# 02_-_GSM.net
KiCad netlist of a schematic drawn in Altium Designer
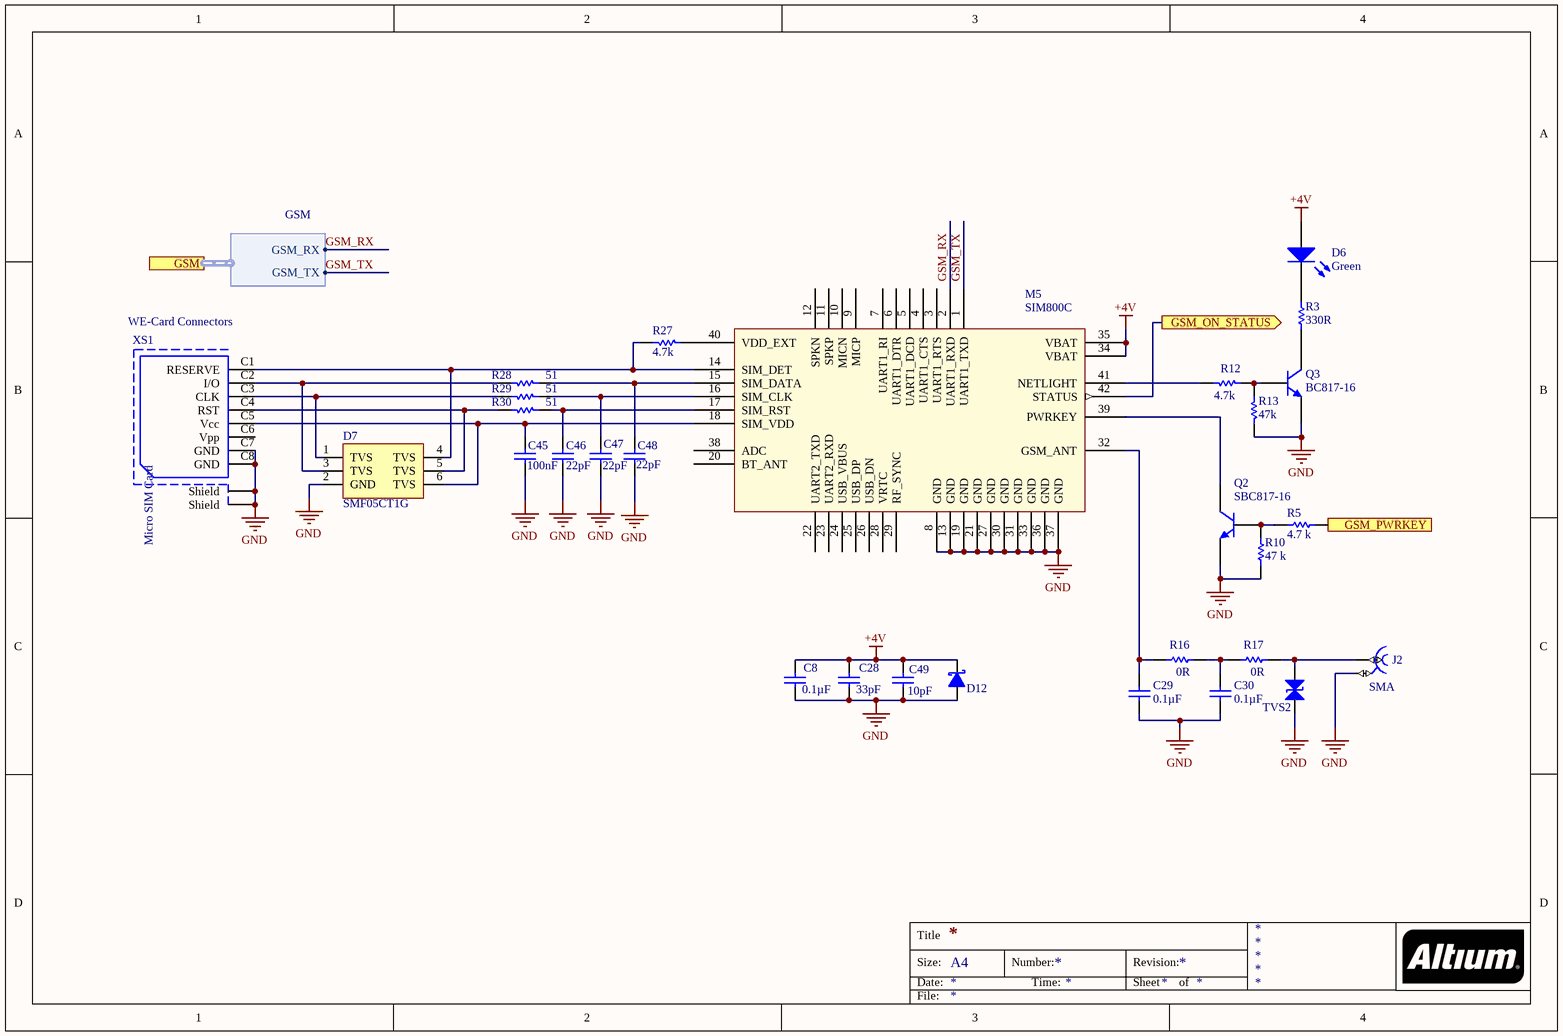
[diagram p0: [02] - GSM.SchDoc]

(export (version "E")
  (design (tool "Eeschema 10.0.6"))
  (components
    (comp (ref "C8")
      (value "Capacitor")
      (footprint "Blue Tractor-2021:0603_C")
      (description "Chip Capacitor Nonpolar")
      (fields
        (field (name "MANUFACTURER") "Kemet")
        (field (name "MANUFACTURER PART NUMBER") "C0603C104K5RACTU")
        (field (name "CAPACITANCE") "0.1µF")
      )
      (libsource (lib "Altium_Library") (part "Capacitor"))
    )
    (comp (ref "C28")
      (value "Capacitor")
      (footprint "Blue Tractor-2021:0603_C")
      (description "Chip Capacitor Nonpolar")
      (fields
        (field (name "MANUFACTURER") "Kemet")
        (field (name "MANUFACTURER PART NUMBER") "C0603C104K5RACTU")
        (field (name "CAPACITANCE") "33pF")
      )
      (libsource (lib "Altium_Library") (part "Capacitor"))
    )
    (comp (ref "C29")
      (value "Capacitor")
      (footprint "Blue Tractor-2021:0603_C")
      (description "Chip Capacitor Nonpolar")
      (fields
        (field (name "MANUFACTURER") "Kemet")
        (field (name "MANUFACTURER PART NUMBER") "C0603C104K5RACTU")
        (field (name "CAPACITANCE") "0.1µF")
      )
      (libsource (lib "Altium_Library") (part "Capacitor"))
    )
    (comp (ref "C30")
      (value "Capacitor")
      (footprint "Blue Tractor-2021:0603_C")
      (description "Chip Capacitor Nonpolar")
      (fields
        (field (name "MANUFACTURER") "Kemet")
        (field (name "MANUFACTURER PART NUMBER") "C0603C104K5RACTU")
        (field (name "CAPACITANCE") "0.1µF")
      )
      (libsource (lib "Altium_Library") (part "Capacitor"))
    )
    (comp (ref "C45")
      (value "Capacitor")
      (footprint "Blue Tractor-2021:0603_C")
      (description "Chip Capacitor Nonpolar")
      (fields
        (field (name "MANUFACTURER") "Kemet")
        (field (name "MANUFACTURER PART NUMBER") "C0603C104K5RACTU")
        (field (name "CAPACITANCE") "100nF")
      )
      (libsource (lib "Altium_Library") (part "Capacitor"))
    )
    (comp (ref "C46")
      (value "Capacitor")
      (footprint "Blue Tractor-2021:0603_C")
      (description "Chip Capacitor Nonpolar")
      (fields
        (field (name "MANUFACTURER") "Kemet")
        (field (name "MANUFACTURER PART NUMBER") "C0603C104K5RACTU")
        (field (name "CAPACITANCE") "22pF")
      )
      (libsource (lib "Altium_Library") (part "Capacitor"))
    )
    (comp (ref "C47")
      (value "Capacitor")
      (footprint "Blue Tractor-2021:0603_C")
      (description "Chip Capacitor Nonpolar")
      (fields
        (field (name "MANUFACTURER") "Kemet")
        (field (name "MANUFACTURER PART NUMBER") "C0603C104K5RACTU")
        (field (name "CAPACITANCE") "22pF")
      )
      (libsource (lib "Altium_Library") (part "Capacitor"))
    )
    (comp (ref "C48")
      (value "Capacitor")
      (footprint "Blue Tractor-2021:0603_C")
      (description "Chip Capacitor Nonpolar")
      (fields
        (field (name "MANUFACTURER") "Kemet")
        (field (name "MANUFACTURER PART NUMBER") "C0603C104K5RACTU")
        (field (name "CAPACITANCE") "22pF")
      )
      (libsource (lib "Altium_Library") (part "Capacitor"))
    )
    (comp (ref "C49")
      (value "Capacitor")
      (footprint "Blue Tractor-2021:0603_C")
      (description "Chip Capacitor Nonpolar")
      (fields
        (field (name "MANUFACTURER") "Kemet")
        (field (name "MANUFACTURER PART NUMBER") "C0603C104K5RACTU")
        (field (name "CAPACITANCE") "10pF")
      )
      (libsource (lib "Altium_Library") (part "Capacitor"))
    )
    (comp (ref "D6")
      (value "LED")
      (footprint "Blue Tractor-2021:Led 0805 green")
      (description "Led 0805")
      (fields
        (field (name "MANUFACTURER") "Vishay Lite-On")
        (field (name "MANUFACTURER PART NUMBER") "LTST-S220GKT")
        (field (name "COLOUR") "Green")
      )
      (libsource (lib "Altium_Library") (part "LED"))
    )
    (comp (ref "D7")
      (value "SMF05CT1G")
      (footprint "Blue Tractor-2021:? TVS SMF05CT")
      (description "5-Line Transient Voltage  Suppressor Array")
      (fields (field (name "MANUFACTURER") "ON Semiconductor"))
      (libsource (lib "SIM68V") (part "SMF05CT1G"))
    )
    (comp (ref "D12")
      (value "D Schottky_1")
      (footprint "Blue Tractor-2021:SOD-323")
      (description "SMAZ16-13-F")
      (fields (field (name "MANUFACTURER") "Diodes Incorporated"))
      (libsource (lib "Blue Tractor-2021") (part "D Schottky_1"))
    )
    (comp (ref "J2")
      (value "SMA")
      (footprint "Blue Tractor-2021:AMPHENOL_132134")
      (fields
        (field (name "MANUFACTURER") "TE Connectivity")
        (field (name "MANUFACTURER PART NUMBER") "5-1814832-1")
        (field (name "AUTHOR") "CERN DEM JLC")
      )
      (libsource (lib "Connectors") (part "Coax_1Female_1Shield"))
    )
    (comp (ref "M5")
      (value "SIM800C")
      (footprint "Blue Tractor-2021:GSM SIM800C")
      (description "GSM/GPS module")
      (libsource (lib "Blue Tractor-2021") (part "SIM800C"))
    )
    (comp (ref "Q2")
      (value "SBC817-16")
      (footprint "SOT23-3")
      (description "NPN General-purpose Transistor")
      (fields
        (field (name "MANUFACTURER") "ON Semiconductor")
        (field (name "MANUFACTURER PART NUMBER") "BC817-16LT3G")
      )
      (libsource (lib "Blue Tractor-2021") (part "BC817-16"))
    )
    (comp (ref "Q3")
      (value "BC817-16")
      (footprint "SOT23-3")
      (description "NPN General-purpose Transistor")
      (fields
        (field (name "MANUFACTURER") "ON Semiconductor")
        (field (name "MANUFACTURER PART NUMBER") "BC817-16LT3G")
      )
      (libsource (lib "Philips Discrete BJT - Low Power") (part "BC817-16"))
    )
    (comp (ref "R3")
      (value "Res1")
      (footprint "Blue Tractor-2021:0603_R")
      (description "Chip Resistor")
      (fields
        (field (name "MANUFACTURER") "Panasonic")
        (field (name "MANUFACTURER PART NUMBER") "ERJ-3GEYJ103V")
        (field (name "RESISTANCE") "330R")
      )
      (libsource (lib "Blue Tractor-2021") (part "Res1"))
    )
    (comp (ref "R5")
      (value "Res1")
      (footprint "Blue Tractor-2021:0603_R")
      (description "Chip Resistor")
      (fields
        (field (name "MANUFACTURER") "Panasonic")
        (field (name "MANUFACTURER PART NUMBER") "ERJ-3GEYJ103V")
        (field (name "RESISTANCE") "4.7 k")
      )
      (libsource (lib "Altium_Library") (part "Res1"))
    )
    (comp (ref "R10")
      (value "Res1")
      (footprint "Blue Tractor-2021:0603_R")
      (description "Chip Resistor")
      (fields
        (field (name "MANUFACTURER") "Panasonic")
        (field (name "MANUFACTURER PART NUMBER") "ERJ-3GEYJ103V")
        (field (name "RESISTANCE") "47 k")
      )
      (libsource (lib "Altium_Library") (part "Res1"))
    )
    (comp (ref "R12")
      (value "Res1")
      (footprint "Blue Tractor-2021:0603_R")
      (description "Chip Resistor")
      (fields
        (field (name "MANUFACTURER") "Panasonic")
        (field (name "MANUFACTURER PART NUMBER") "ERJ-3EKF3300V")
        (field (name "RESISTANCE") "4.7k")
      )
      (libsource (lib "Altium_Library") (part "Res1"))
    )
    (comp (ref "R13")
      (value "Res1")
      (footprint "Blue Tractor-2021:0603_R")
      (description "Chip Resistor")
      (fields
        (field (name "MANUFACTURER") "Panasonic")
        (field (name "MANUFACTURER PART NUMBER") "ERJ-3EKF3300V")
        (field (name "RESISTANCE") "47k")
      )
      (libsource (lib "Altium_Library") (part "Res1"))
    )
    (comp (ref "R16")
      (value "Res1")
      (footprint "Blue Tractor-2021:0603_R")
      (description "Chip Resistor")
      (fields
        (field (name "MANUFACTURER") "Panasonic")
        (field (name "MANUFACTURER PART NUMBER") "ERJ-3GEY0R00V")
        (field (name "RESISTANCE") "0R")
      )
      (libsource (lib "Altium_Library") (part "Res1"))
    )
    (comp (ref "R17")
      (value "Res1")
      (footprint "Blue Tractor-2021:0603_R")
      (description "Chip Resistor")
      (fields
        (field (name "MANUFACTURER") "Panasonic")
        (field (name "MANUFACTURER PART NUMBER") "ERJ-3GEY0R00V")
        (field (name "RESISTANCE") "0R")
      )
      (libsource (lib "Altium_Library") (part "Res1"))
    )
    (comp (ref "R27")
      (value "Res1")
      (footprint "Blue Tractor-2021:0603_R")
      (description "Chip Resistor")
      (fields
        (field (name "MANUFACTURER") "Panasonic")
        (field (name "MANUFACTURER PART NUMBER") "ERJ-3EKF3300V")
        (field (name "RESISTANCE") "4.7k")
      )
      (libsource (lib "Altium_Library") (part "Res1"))
    )
    (comp (ref "R28")
      (value "Res1")
      (footprint "Blue Tractor-2021:0603_R")
      (description "Chip Resistor")
      (fields
        (field (name "MANUFACTURER") "Panasonic")
        (field (name "MANUFACTURER PART NUMBER") "ERJ-3EKF3300V")
        (field (name "RESISTANCE") "51")
      )
      (libsource (lib "Altium_Library") (part "Res1"))
    )
    (comp (ref "R29")
      (value "Res1")
      (footprint "Blue Tractor-2021:0603_R")
      (description "Chip Resistor")
      (fields
        (field (name "MANUFACTURER") "Panasonic")
        (field (name "MANUFACTURER PART NUMBER") "ERJ-3EKF3300V")
        (field (name "RESISTANCE") "51")
      )
      (libsource (lib "Altium_Library") (part "Res1"))
    )
    (comp (ref "R30")
      (value "Res1")
      (footprint "Blue Tractor-2021:0603_R")
      (description "Chip Resistor")
      (fields
        (field (name "MANUFACTURER") "Panasonic")
        (field (name "MANUFACTURER PART NUMBER") "ERJ-3EKF3300V")
        (field (name "RESISTANCE") "51")
      )
      (libsource (lib "Altium_Library") (part "Res1"))
    )
    (comp (ref "TVS2")
      (value "LXE15AAA1-153")
      (footprint "Blue Tractor-2021:LXES15_MUR-L")
      (libsource (lib "Blue Tractor-2021") (part "TVS-LXE15AAA1-153"))
    )
    (comp (ref "XS1")
      (value "WE-Card Connectors")
      (footprint "Blue Tractor-2021:693022010811")
      (description "WR-CRD Micro SIM_Hinge_8 pins")
      (fields
        (field (name "MANUFACTURER") "Würth Elektronik eiSos GmbH")
        (field (name "PARTNO") "693022010811")
        (field (name "CREATED BY") "Karrer Zheng")
      )
      (libsource (lib "Blue Tractor-2021") (part "WE-Card Connectors 693022010811"))
    )
  )
  (nets
    (net (code "2") (name "+4V") (class "Default")
      (node (ref "C28") (pin "2") (pinfunction "2_2") (pintype "passive"))
      (node (ref "C49") (pin "2") (pinfunction "2_2") (pintype "passive"))
      (node (ref "C8") (pin "2") (pinfunction "2_2") (pintype "passive"))
      (node (ref "D12") (pin "1") (pinfunction "K_1") (pintype "passive"))
      (node (ref "D6") (pin "1") (pinfunction "A_1") (pintype "passive"))
      (node (ref "M5") (pin "34") (pinfunction "VBAT_34") (pintype "power_in"))
      (node (ref "M5") (pin "35") (pinfunction "VBAT_35") (pintype "power_in"))
    )
    (net (code "3") (name "/GSM_ON_STATUS") (class "Default")
      (node (ref "M5") (pin "42") (pinfunction "STATUS_42") (pintype "output"))
    )
    (net (code "4") (name "/GSM_PWRKEY") (class "Default")
      (node (ref "R5") (pin "2") (pinfunction "2_2") (pintype "passive"))
    )
    (net (code "5") (name "/GSM_RX") (class "Default")
      (node (ref "M5") (pin "2") (pinfunction "UART1_RXD_2") (pintype "power_in"))
    )
    (net (code "6") (name "/GSM_TX") (class "Default")
      (node (ref "M5") (pin "1") (pinfunction "UART1_TXD_1") (pintype "power_in"))
    )
    (net (code "8") (name "GND") (class "Default")
      (node (ref "C28") (pin "1") (pinfunction "1_1") (pintype "passive"))
      (node (ref "C29") (pin "1") (pinfunction "1_1") (pintype "passive"))
      (node (ref "C30") (pin "1") (pinfunction "1_1") (pintype "passive"))
      (node (ref "C45") (pin "1") (pinfunction "1_1") (pintype "passive"))
      (node (ref "C46") (pin "1") (pinfunction "1_1") (pintype "passive"))
      (node (ref "C47") (pin "1") (pinfunction "1_1") (pintype "passive"))
      (node (ref "C48") (pin "1") (pinfunction "1_1") (pintype "passive"))
      (node (ref "C49") (pin "1") (pinfunction "1_1") (pintype "passive"))
      (node (ref "C8") (pin "1") (pinfunction "1_1") (pintype "passive"))
      (node (ref "D12") (pin "2") (pinfunction "A_2") (pintype "passive"))
      (node (ref "D7") (pin "2") (pinfunction "GND_2") (pintype "passive"))
      (node (ref "J2") (pin "2") (pinfunction "2_2") (pintype "bidirectional"))
      (node (ref "M5") (pin "13") (pinfunction "GND_13") (pintype "passive"))
      (node (ref "M5") (pin "19") (pinfunction "GND_19") (pintype "passive"))
      (node (ref "M5") (pin "21") (pinfunction "GND_21") (pintype "passive"))
      (node (ref "M5") (pin "27") (pinfunction "GND_27") (pintype "passive"))
      (node (ref "M5") (pin "30") (pinfunction "GND_30") (pintype "passive"))
      (node (ref "M5") (pin "31") (pinfunction "GND_31") (pintype "passive"))
      (node (ref "M5") (pin "33") (pinfunction "GND_33") (pintype "power_in"))
      (node (ref "M5") (pin "36") (pinfunction "GND_36") (pintype "power_in"))
      (node (ref "M5") (pin "37") (pinfunction "GND_37") (pintype "power_in"))
      (node (ref "M5") (pin "8") (pinfunction "GND_8") (pintype "passive"))
      (node (ref "Q2") (pin "2") (pinfunction "E_2") (pintype "passive"))
      (node (ref "Q3") (pin "2") (pinfunction "E_2") (pintype "passive"))
      (node (ref "R10") (pin "1") (pinfunction "1_1") (pintype "passive"))
      (node (ref "R13") (pin "1") (pinfunction "1_1") (pintype "passive"))
      (node (ref "TVS2") (pin "1") (pinfunction "1_1") (pintype "passive"))
      (node (ref "XS1") (pin "C7") (pinfunction "GND_C7") (pintype "passive"))
      (node (ref "XS1") (pin "C8") (pinfunction "GND_C8") (pintype "passive"))
      (node (ref "XS1") (pin "Z1") (pinfunction "Shield_Z1") (pintype "passive"))
      (node (ref "XS1") (pin "Z2") (pinfunction "Shield_Z2") (pintype "passive"))
    )
    (net (code "9") (name "Net-(C30-Pad2)") (class "Default")
      (node (ref "C30") (pin "2") (pinfunction "2_2") (pintype "passive"))
      (node (ref "R16") (pin "1") (pinfunction "1_1") (pintype "passive"))
      (node (ref "R17") (pin "2") (pinfunction "2_2") (pintype "passive"))
    )
    (net (code "10") (name "Net-(D6-K)") (class "Default")
      (node (ref "D6") (pin "2") (pinfunction "K_2") (pintype "passive"))
      (node (ref "R3") (pin "2") (pinfunction "2_2") (pintype "passive"))
    )
    (net (code "11") (name "Net-(J2-Pad1)") (class "Default")
      (node (ref "J2") (pin "1") (pinfunction "1_1") (pintype "bidirectional"))
      (node (ref "R17") (pin "1") (pinfunction "1_1") (pintype "passive"))
      (node (ref "TVS2") (pin "2") (pinfunction "2_2") (pintype "passive"))
    )
    (net (code "12") (name "Net-(M5-GSM_ANT)") (class "Default")
      (node (ref "C29") (pin "2") (pinfunction "2_2") (pintype "passive"))
      (node (ref "M5") (pin "32") (pinfunction "GSM_ANT_32") (pintype "passive"))
      (node (ref "R16") (pin "2") (pinfunction "2_2") (pintype "passive"))
    )
    (net (code "13") (name "Net-(M5-NETLIGHT)") (class "Default")
      (node (ref "M5") (pin "41") (pinfunction "NETLIGHT_41") (pintype "power_in"))
      (node (ref "R12") (pin "1") (pinfunction "1_1") (pintype "passive"))
    )
    (net (code "14") (name "Net-(M5-PWRKEY)") (class "Default")
      (node (ref "M5") (pin "39") (pinfunction "PWRKEY_39") (pintype "power_in"))
      (node (ref "Q2") (pin "3") (pinfunction "C_3") (pintype "passive"))
    )
    (net (code "15") (name "Net-(M5-SIM_CLK)") (class "Default")
      (node (ref "C47") (pin "2") (pinfunction "2_2") (pintype "passive"))
      (node (ref "M5") (pin "16") (pinfunction "SIM_CLK_16") (pintype "passive"))
      (node (ref "R29") (pin "1") (pinfunction "1_1") (pintype "passive"))
    )
    (net (code "16") (name "Net-(M5-SIM_DATA)") (class "Default")
      (node (ref "C48") (pin "2") (pinfunction "2_2") (pintype "passive"))
      (node (ref "M5") (pin "15") (pinfunction "SIM_DATA_15") (pintype "passive"))
      (node (ref "R28") (pin "1") (pinfunction "1_1") (pintype "passive"))
    )
    (net (code "17") (name "Net-(M5-SIM_DET)") (class "Default")
      (node (ref "D7") (pin "4") (pinfunction "TVS_4") (pintype "passive"))
      (node (ref "M5") (pin "14") (pinfunction "SIM_DET_14") (pintype "passive"))
      (node (ref "R27") (pin "2") (pinfunction "2_2") (pintype "passive"))
      (node (ref "XS1") (pin "C1") (pinfunction "RESERVE_C1") (pintype "passive"))
    )
    (net (code "18") (name "Net-(M5-SIM_RST)") (class "Default")
      (node (ref "C46") (pin "2") (pinfunction "2_2") (pintype "passive"))
      (node (ref "M5") (pin "17") (pinfunction "SIM_RST_17") (pintype "passive"))
      (node (ref "R30") (pin "1") (pinfunction "1_1") (pintype "passive"))
    )
    (net (code "19") (name "Net-(M5-SIM_VDD)") (class "Default")
      (node (ref "C45") (pin "2") (pinfunction "2_2") (pintype "passive"))
      (node (ref "D7") (pin "6") (pinfunction "TVS_6") (pintype "passive"))
      (node (ref "M5") (pin "18") (pinfunction "SIM_VDD_18") (pintype "passive"))
      (node (ref "XS1") (pin "C5") (pinfunction "Vcc_C5") (pintype "passive"))
    )
    (net (code "20") (name "Net-(M5-VDD_EXT)") (class "Default")
      (node (ref "M5") (pin "40") (pinfunction "VDD_EXT_40") (pintype "power_in"))
      (node (ref "R27") (pin "1") (pinfunction "1_1") (pintype "passive"))
    )
    (net (code "21") (name "Net-(Q2-B)") (class "Default")
      (node (ref "Q2") (pin "1") (pinfunction "B_1") (pintype "passive"))
      (node (ref "R10") (pin "2") (pinfunction "2_2") (pintype "passive"))
      (node (ref "R5") (pin "1") (pinfunction "1_1") (pintype "passive"))
    )
    (net (code "22") (name "Net-(Q3-B)") (class "Default")
      (node (ref "Q3") (pin "1") (pinfunction "B_1") (pintype "passive"))
      (node (ref "R12") (pin "2") (pinfunction "2_2") (pintype "passive"))
      (node (ref "R13") (pin "2") (pinfunction "2_2") (pintype "passive"))
    )
    (net (code "23") (name "Net-(Q3-C)") (class "Default")
      (node (ref "Q3") (pin "3") (pinfunction "C_3") (pintype "passive"))
      (node (ref "R3") (pin "1") (pinfunction "1_1") (pintype "passive"))
    )
    (net (code "24") (name "Net-(XS1-CLK)") (class "Default")
      (node (ref "D7") (pin "1") (pinfunction "TVS_1") (pintype "passive"))
      (node (ref "R29") (pin "2") (pinfunction "2_2") (pintype "passive"))
      (node (ref "XS1") (pin "C3") (pinfunction "CLK_C3") (pintype "passive"))
    )
    (net (code "25") (name "Net-(XS1-I{slash}O)") (class "Default")
      (node (ref "D7") (pin "3") (pinfunction "TVS_3") (pintype "passive"))
      (node (ref "R28") (pin "2") (pinfunction "2_2") (pintype "passive"))
      (node (ref "XS1") (pin "C2") (pinfunction "I/O_C2") (pintype "passive"))
    )
    (net (code "26") (name "Net-(XS1-RST)") (class "Default")
      (node (ref "D7") (pin "5") (pinfunction "TVS_5") (pintype "passive"))
      (node (ref "R30") (pin "2") (pinfunction "2_2") (pintype "passive"))
      (node (ref "XS1") (pin "C4") (pinfunction "RST_C4") (pintype "passive"))
    )
    (net (code "27") (name "unconnected-(M5-ADC-Pad38)") (class "Default")
      (node (ref "M5") (pin "38") (pinfunction "ADC_38") (pintype "power_in"))
    )
    (net (code "28") (name "unconnected-(M5-BT_ANT-Pad20)") (class "Default")
      (node (ref "M5") (pin "20") (pinfunction "BT_ANT_20") (pintype "passive"))
    )
    (net (code "29") (name "unconnected-(M5-MICN-Pad10)") (class "Default")
      (node (ref "M5") (pin "10") (pinfunction "MICN_10") (pintype "passive"))
    )
    (net (code "30") (name "unconnected-(M5-MICP-Pad9)") (class "Default")
      (node (ref "M5") (pin "9") (pinfunction "MICP_9") (pintype "passive"))
    )
    (net (code "31") (name "unconnected-(M5-RF_SYNC-Pad29)") (class "Default")
      (node (ref "M5") (pin "29") (pinfunction "RF_SYNC_29") (pintype "passive"))
    )
    (net (code "32") (name "unconnected-(M5-SPKN-Pad12)") (class "Default")
      (node (ref "M5") (pin "12") (pinfunction "SPKN_12") (pintype "passive"))
    )
    (net (code "33") (name "unconnected-(M5-SPKP-Pad11)") (class "Default")
      (node (ref "M5") (pin "11") (pinfunction "SPKP_11") (pintype "passive"))
    )
    (net (code "34") (name "unconnected-(M5-UART1_CTS-Pad4)") (class "Default")
      (node (ref "M5") (pin "4") (pinfunction "UART1_CTS_4") (pintype "passive"))
    )
    (net (code "35") (name "unconnected-(M5-UART1_DCD-Pad5)") (class "Default")
      (node (ref "M5") (pin "5") (pinfunction "UART1_DCD_5") (pintype "passive"))
    )
    (net (code "36") (name "unconnected-(M5-UART1_DTR-Pad6)") (class "Default")
      (node (ref "M5") (pin "6") (pinfunction "UART1_DTR_6") (pintype "passive"))
    )
    (net (code "37") (name "unconnected-(M5-UART1_RI-Pad7)") (class "Default")
      (node (ref "M5") (pin "7") (pinfunction "UART1_RI_7") (pintype "passive"))
    )
    (net (code "38") (name "unconnected-(M5-UART1_RTS-Pad3)") (class "Default")
      (node (ref "M5") (pin "3") (pinfunction "UART1_RTS_3") (pintype "power_in"))
    )
    (net (code "39") (name "unconnected-(M5-UART2_RXD-Pad23)") (class "Default")
      (node (ref "M5") (pin "23") (pinfunction "UART2_RXD_23") (pintype "passive"))
    )
    (net (code "40") (name "unconnected-(M5-UART2_TXD-Pad22)") (class "Default")
      (node (ref "M5") (pin "22") (pinfunction "UART2_TXD_22") (pintype "passive"))
    )
    (net (code "41") (name "unconnected-(M5-USB_DN-Pad26)") (class "Default")
      (node (ref "M5") (pin "26") (pinfunction "USB_DN_26") (pintype "passive"))
    )
    (net (code "42") (name "unconnected-(M5-USB_DP-Pad25)") (class "Default")
      (node (ref "M5") (pin "25") (pinfunction "USB_DP_25") (pintype "passive"))
    )
    (net (code "43") (name "unconnected-(M5-USB_VBUS-Pad24)") (class "Default")
      (node (ref "M5") (pin "24") (pinfunction "USB_VBUS_24") (pintype "passive"))
    )
    (net (code "44") (name "unconnected-(M5-VRTC-Pad28)") (class "Default")
      (node (ref "M5") (pin "28") (pinfunction "VRTC_28") (pintype "passive"))
    )
    (net (code "45") (name "unconnected-(XS1-Vpp-PadC6)") (class "Default")
      (node (ref "XS1") (pin "C6") (pinfunction "Vpp_C6") (pintype "passive"))
    )
  )
)
